# windVane.net
KiCad netlist of a schematic drawn in EAGLE
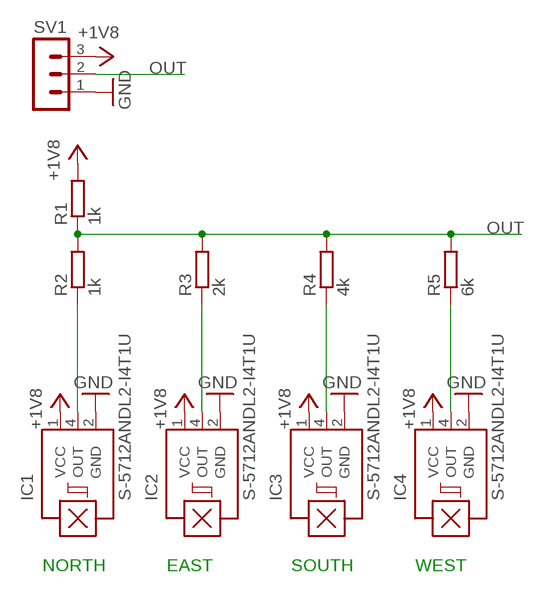
[diagram p0: schematic, sheet 1]

(export (version "E")
  (design (tool "Eeschema 10.0.6"))
  (components
    (comp (ref "IC1")
      (value "S-5712ANDL2-I4T1U")
      (footprint "eagle-import:SNT-4A")
      (libsource (lib "eagle-import") (part "S-5712ANDL2-I4T1U"))
    )
    (comp (ref "IC2")
      (value "S-5712ANDL2-I4T1U")
      (footprint "eagle-import:SNT-4A")
      (libsource (lib "eagle-import") (part "S-5712ANDL2-I4T1U"))
    )
    (comp (ref "IC3")
      (value "S-5712ANDL2-I4T1U")
      (footprint "eagle-import:SNT-4A")
      (libsource (lib "eagle-import") (part "S-5712ANDL2-I4T1U"))
    )
    (comp (ref "IC4")
      (value "S-5712ANDL2-I4T1U")
      (footprint "eagle-import:SNT-4A")
      (libsource (lib "eagle-import") (part "S-5712ANDL2-I4T1U"))
    )
    (comp (ref "R1")
      (value "1k")
      (footprint "eagle-import:M1206")
      (libsource (lib "eagle-import") (part "R-EU_M1206"))
    )
    (comp (ref "R2")
      (value "1k")
      (footprint "eagle-import:M1206")
      (libsource (lib "eagle-import") (part "R-EU_M1206"))
    )
    (comp (ref "R3")
      (value "2k")
      (footprint "eagle-import:M1206")
      (libsource (lib "eagle-import") (part "R-EU_M1206"))
    )
    (comp (ref "R4")
      (value "4k")
      (footprint "eagle-import:M1206")
      (libsource (lib "eagle-import") (part "R-EU_M1206"))
    )
    (comp (ref "R5")
      (value "6k")
      (footprint "eagle-import:M1206")
      (libsource (lib "eagle-import") (part "R-EU_M1206"))
    )
    (comp (ref "SV1")
      (value "MA03-1")
      (footprint "eagle-import:MA03-1")
      (libsource (lib "eagle-import") (part "MA03-1"))
    )
  )
  (nets
    (net (code "1") (name "+1V8") (class "Default")
      (node (ref "IC1") (pin "1") (pinfunction "VCC_1") (pintype "power_in"))
      (node (ref "IC2") (pin "1") (pinfunction "VCC_1") (pintype "power_in"))
      (node (ref "IC3") (pin "1") (pinfunction "VCC_1") (pintype "power_in"))
      (node (ref "IC4") (pin "1") (pinfunction "VCC_1") (pintype "power_in"))
      (node (ref "R1") (pin "2") (pinfunction "2_2") (pintype "passive"))
      (node (ref "SV1") (pin "3") (pinfunction "3_3") (pintype "passive"))
    )
    (net (code "2") (name "/OUT") (class "Default")
      (node (ref "R1") (pin "1") (pinfunction "1_1") (pintype "passive"))
      (node (ref "R2") (pin "2") (pinfunction "2_2") (pintype "passive"))
      (node (ref "R3") (pin "2") (pinfunction "2_2") (pintype "passive"))
      (node (ref "R4") (pin "2") (pinfunction "2_2") (pintype "passive"))
      (node (ref "R5") (pin "2") (pinfunction "2_2") (pintype "passive"))
      (node (ref "SV1") (pin "2") (pinfunction "2_2") (pintype "passive"))
    )
    (net (code "3") (name "GND") (class "Default")
      (node (ref "IC1") (pin "2") (pinfunction "GND_2") (pintype "power_in"))
      (node (ref "IC2") (pin "2") (pinfunction "GND_2") (pintype "power_in"))
      (node (ref "IC3") (pin "2") (pinfunction "GND_2") (pintype "power_in"))
      (node (ref "IC4") (pin "2") (pinfunction "GND_2") (pintype "power_in"))
      (node (ref "SV1") (pin "1") (pinfunction "1_1") (pintype "passive"))
    )
    (net (code "4") (name "Net-(IC1-OUT)") (class "Default")
      (node (ref "IC1") (pin "4") (pinfunction "OUT_4") (pintype "output"))
      (node (ref "R2") (pin "1") (pinfunction "1_1") (pintype "passive"))
    )
    (net (code "5") (name "Net-(IC2-OUT)") (class "Default")
      (node (ref "IC2") (pin "4") (pinfunction "OUT_4") (pintype "output"))
      (node (ref "R3") (pin "1") (pinfunction "1_1") (pintype "passive"))
    )
    (net (code "6") (name "Net-(IC3-OUT)") (class "Default")
      (node (ref "IC3") (pin "4") (pinfunction "OUT_4") (pintype "output"))
      (node (ref "R4") (pin "1") (pinfunction "1_1") (pintype "passive"))
    )
    (net (code "7") (name "Net-(IC4-OUT)") (class "Default")
      (node (ref "IC4") (pin "4") (pinfunction "OUT_4") (pintype "output"))
      (node (ref "R5") (pin "1") (pinfunction "1_1") (pintype "passive"))
    )
  )
)
